# cm3.net
KiCad netlist of a schematic drawn in EAGLE
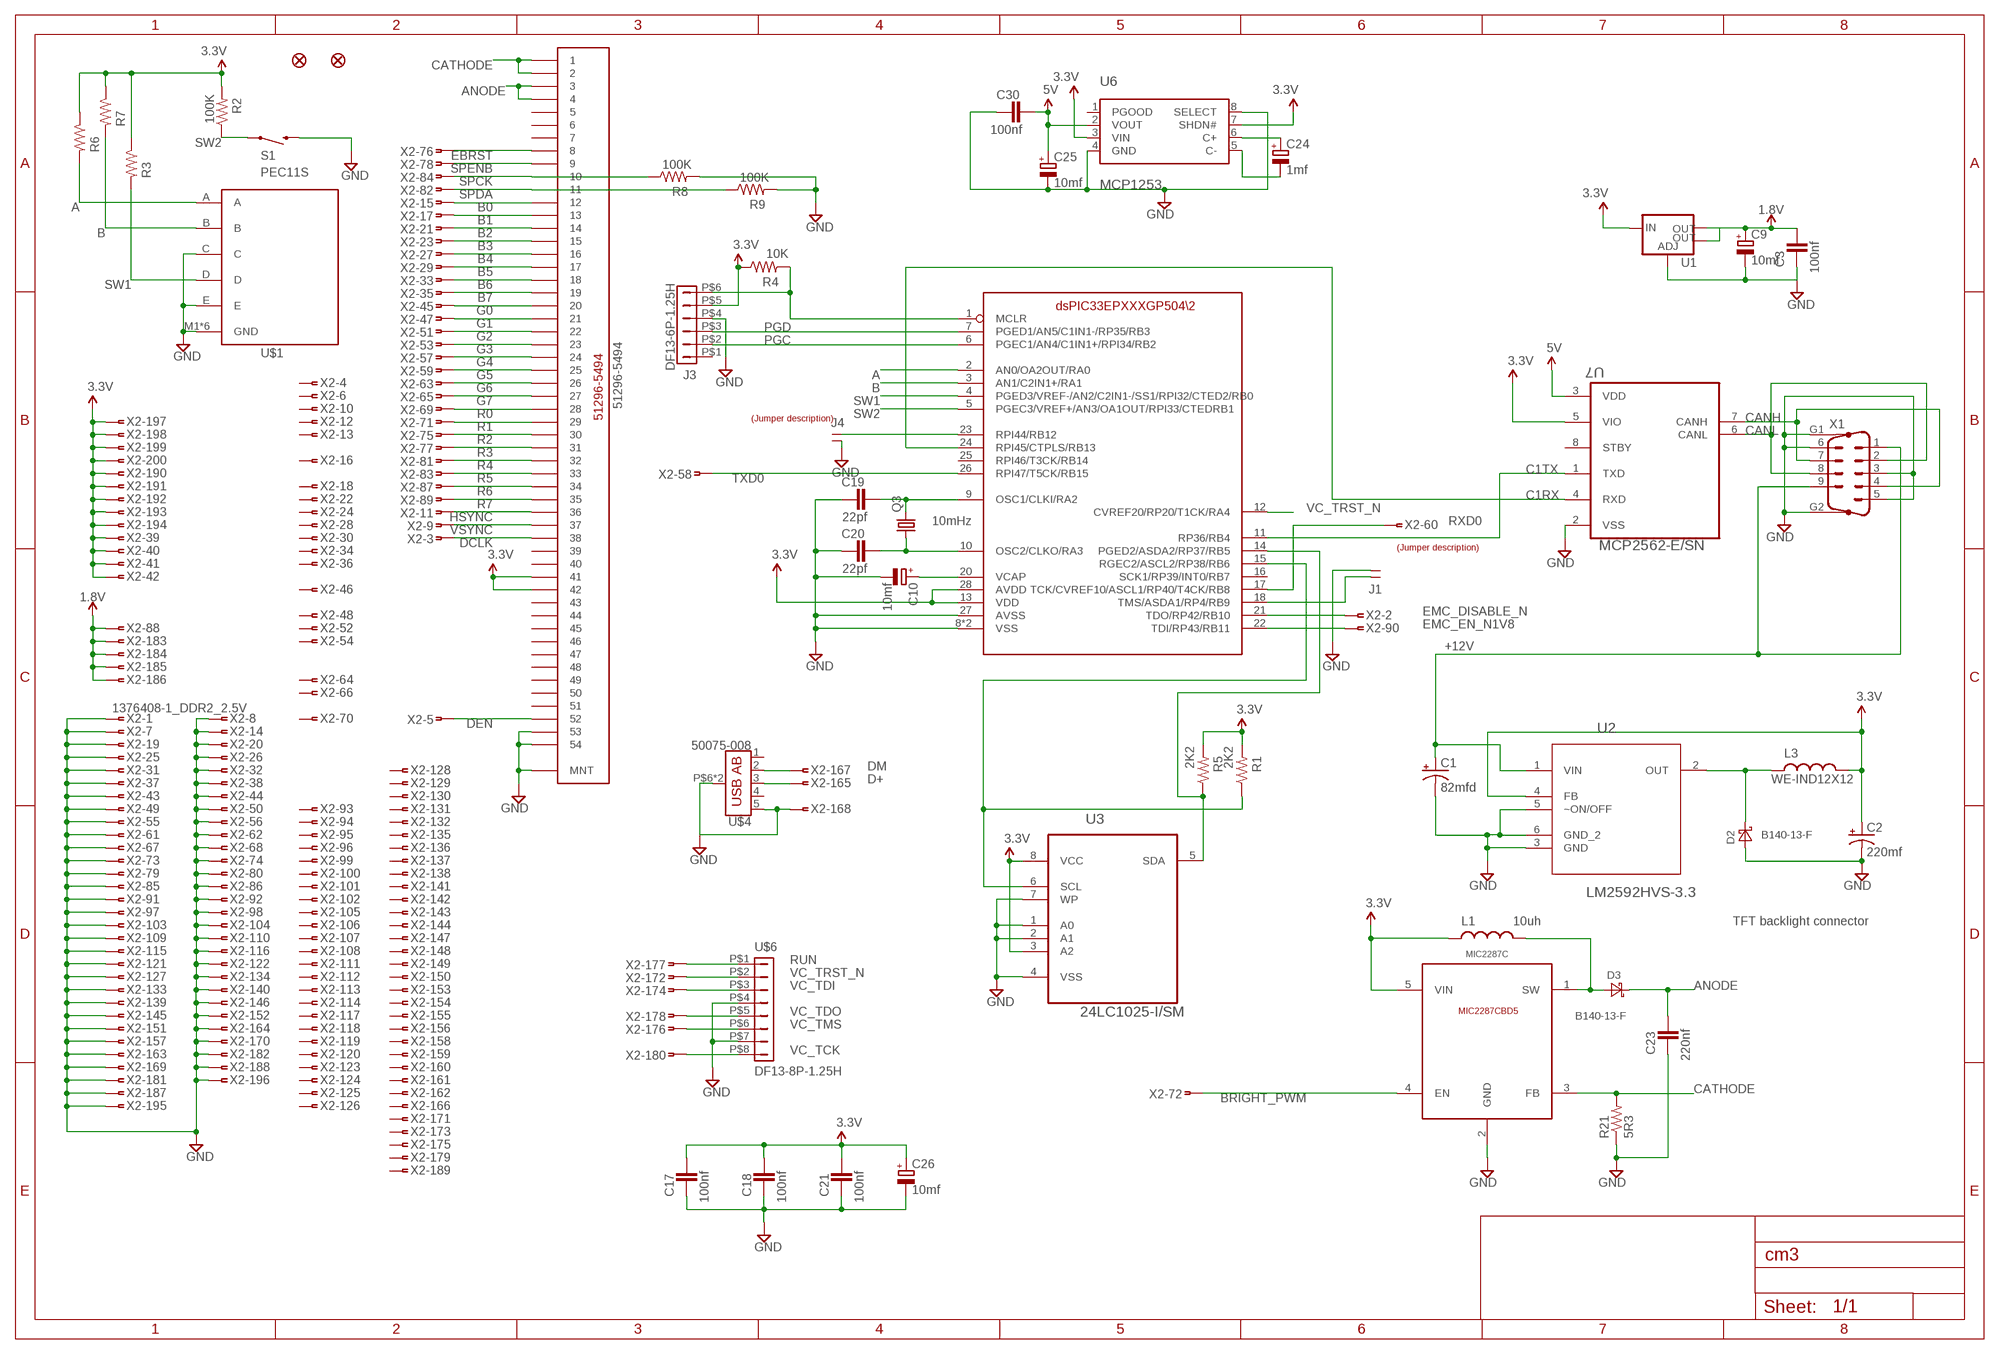
[diagram p0: schematic, sheet 1]

(export (version "E")
  (design (tool "Eeschema 10.0.6"))
  (components
    (comp (ref "C1")
      (value "82mfd")
      (footprint "eagle-import:SVPF-E7")
      (libsource (lib "eagle-import") (part "CAPACITOR_POL-SVPF-E7"))
    )
    (comp (ref "C2")
      (value "220mf")
      (footprint "eagle-import:EIA7343")
      (fields (field (name "PARTNO") "T545X227M016ATE035"))
      (libsource (lib "eagle-import") (part "CAP_POL7343"))
    )
    (comp (ref "C3")
      (value "100nf")
      (footprint "eagle-import:C805")
      (fields (field (name "PARTNO") "CL21F104ZBCNNNC"))
      (libsource (lib "eagle-import") (part "CAPACITOR_NPOL-0805"))
    )
    (comp (ref "C9")
      (value "10mf")
      (footprint "eagle-import:SMC_A")
      (fields (field (name "PARTNO") "T491A106K004AT"))
      (libsource (lib "eagle-import") (part "CAPACITOR_POL-SMC_A"))
    )
    (comp (ref "C10")
      (value "10mf")
      (footprint "eagle-import:SMC_A")
      (fields (field (name "PARTNO") "T491A106K004AT"))
      (libsource (lib "eagle-import") (part "CAPACITOR_POL-SMC_A"))
    )
    (comp (ref "C17")
      (value "100nf")
      (footprint "eagle-import:C805")
      (fields (field (name "PARTNO") "CL21F104ZBCNNNC"))
      (libsource (lib "eagle-import") (part "CAPACITOR_NPOL-0805"))
    )
    (comp (ref "C18")
      (value "100nf")
      (footprint "eagle-import:C805")
      (fields (field (name "PARTNO") "CL21F104ZBCNNNC"))
      (libsource (lib "eagle-import") (part "CAPACITOR_NPOL-0805"))
    )
    (comp (ref "C19")
      (value "22pf")
      (footprint "eagle-import:C805")
      (fields (field (name "PARTNO") "C0805C220J5GACTU"))
      (libsource (lib "eagle-import") (part "CAPACITOR_NPOL-0805"))
    )
    (comp (ref "C20")
      (value "22pf")
      (footprint "eagle-import:C805")
      (fields (field (name "PARTNO") "C0805C220J5GACTU"))
      (libsource (lib "eagle-import") (part "CAPACITOR_NPOL-0805"))
    )
    (comp (ref "C21")
      (value "100nf")
      (footprint "eagle-import:C805")
      (fields (field (name "PARTNO") "CL21F104ZBCNNNC"))
      (libsource (lib "eagle-import") (part "CAPACITOR_NPOL-0805"))
    )
    (comp (ref "C23")
      (value "220nf")
      (footprint "eagle-import:C805")
      (fields (field (name "PARTNO") "CL21F224ZBCNNNC"))
      (libsource (lib "eagle-import") (part "CAPACITOR_NPOL-0805"))
    )
    (comp (ref "C24")
      (value "1mf")
      (footprint "eagle-import:SMC_A")
      (fields (field (name "PARTNO") "F931C105MAA"))
      (libsource (lib "eagle-import") (part "CAPACITOR_POL-SMC_A"))
    )
    (comp (ref "C25")
      (value "10mf")
      (footprint "eagle-import:SMC_A")
      (fields (field (name "PARTNO") "T491A106K004AT"))
      (libsource (lib "eagle-import") (part "CAPACITOR_POL-SMC_A"))
    )
    (comp (ref "C26")
      (value "10mf")
      (footprint "eagle-import:SMC_A")
      (fields (field (name "PARTNO") "T491A106K004AT"))
      (libsource (lib "eagle-import") (part "CAPACITOR_POL-SMC_A"))
    )
    (comp (ref "C30")
      (value "100nf")
      (footprint "eagle-import:C805")
      (fields (field (name "PARTNO") "CL21F104ZBCNNNC"))
      (libsource (lib "eagle-import") (part "CAPACITOR_NPOL-0805"))
    )
    (comp (ref "D2")
      (value "B140-13-F")
      (footprint "eagle-import:SMA")
      (libsource (lib "eagle-import") (part "DIODE-SCHOTTKY-SMA"))
    )
    (comp (ref "D3")
      (value "B140-13-F")
      (footprint "eagle-import:SMA")
      (libsource (lib "eagle-import") (part "DIODE-SCHOTTKY-SMA"))
    )
    (comp (ref "J1")
      (value "JUMPER-1X2")
      (footprint "eagle-import:JUMPER-1X2")
      (fields (field (name "PARTNO") "M20-9770246"))
      (libsource (lib "eagle-import") (part "JUMPER-1X2"))
    )
    (comp (ref "J3")
      (value "DF13-6P-1.25H")
      (footprint "eagle-import:DF13A-6P-1.25H")
      (fields (field (name "PARTNO") "DF13A-6P-1.25H(20)"))
      (libsource (lib "eagle-import") (part "DF13-6P-1.25H"))
    )
    (comp (ref "J4")
      (value "JUMPER-1X2")
      (footprint "eagle-import:JUMPER-1X2")
      (fields (field (name "PARTNO") "M20-9770246"))
      (libsource (lib "eagle-import") (part "JUMPER-1X2"))
    )
    (comp (ref "JP1")
      (value "FIDUCIAL1.5X3")
      (footprint "eagle-import:FIDUCIAL-1.5X3")
      (libsource (lib "eagle-import") (part "FIDUCIAL1.5X3"))
    )
    (comp (ref "JP2")
      (value "FIDUCIAL1.5X3")
      (footprint "eagle-import:FIDUCIAL-1.5X3")
      (libsource (lib "eagle-import") (part "FIDUCIAL1.5X3"))
    )
    (comp (ref "L1")
      (value "10uh")
      (footprint "eagle-import:1812")
      (fields (field (name "PARTNO") "VLF504015MT-100M"))
      (libsource (lib "eagle-import") (part "INDUCTOR"))
    )
    (comp (ref "L3")
      (value "WE-IND12X12")
      (footprint "eagle-import:IND12X12")
      (libsource (lib "eagle-import") (part "WE-IND12X12"))
    )
    (comp (ref "Q3")
      (value "10mHz")
      (footprint "eagle-import:HC49_S")
      (fields (field (name "PARTNO") "ATS100B-E"))
      (libsource (lib "eagle-import") (part "CRYSTALHC49S"))
    )
    (comp (ref "R1")
      (value "2K2")
      (footprint "eagle-import:0603-RES")
      (fields (field (name "PARTNO") "RC0603FR-072K2L"))
      (libsource (lib "eagle-import") (part "SparkFun-Passives_RESISTOR0603-RES"))
    )
    (comp (ref "R2")
      (value "100K")
      (footprint "eagle-import:0603-RES")
      (fields (field (name "PARTNO") "RC0603JR-07100KL"))
      (libsource (lib "eagle-import") (part "SparkFun-Passives_RESISTOR0603-RES"))
    )
    (comp (ref "R3")
      (value "10K")
      (footprint "eagle-import:0603-RES")
      (fields (field (name "PARTNO") "RC0603FR-0710KL"))
      (libsource (lib "eagle-import") (part "SparkFun-Passives_RESISTOR0603-RES"))
    )
    (comp (ref "R4")
      (value "10K")
      (footprint "eagle-import:0603-RES")
      (fields (field (name "PARTNO") "RC0603FR-0710KL"))
      (libsource (lib "eagle-import") (part "SparkFun-Passives_RESISTOR0603-RES"))
    )
    (comp (ref "R5")
      (value "2K2")
      (footprint "eagle-import:0603-RES")
      (fields (field (name "PARTNO") "RC0603FR-072K2L"))
      (libsource (lib "eagle-import") (part "SparkFun-Passives_RESISTOR0603-RES"))
    )
    (comp (ref "R6")
      (value "10K")
      (footprint "eagle-import:0603-RES")
      (fields (field (name "PARTNO") "RC0603FR-0710KL"))
      (libsource (lib "eagle-import") (part "SparkFun-Passives_RESISTOR0603-RES"))
    )
    (comp (ref "R7")
      (value "10K")
      (footprint "eagle-import:0603-RES")
      (fields (field (name "PARTNO") "RC0603FR-0710KL"))
      (libsource (lib "eagle-import") (part "SparkFun-Passives_RESISTOR0603-RES"))
    )
    (comp (ref "R8")
      (value "100K")
      (footprint "eagle-import:0603-RES")
      (fields (field (name "PARTNO") "RC0603JR-07100KL"))
      (libsource (lib "eagle-import") (part "SparkFun-Passives_RESISTOR0603-RES"))
    )
    (comp (ref "R9")
      (value "100K")
      (footprint "eagle-import:0603-RES")
      (fields (field (name "PARTNO") "RC0603JR-07100KL"))
      (libsource (lib "eagle-import") (part "SparkFun-Passives_RESISTOR0603-RES"))
    )
    (comp (ref "R21")
      (value "5R3")
      (footprint "eagle-import:1812")
      (fields (field (name "PARTNO") "RL1218FK-070R604L"))
      (libsource (lib "eagle-import") (part "RESISTOR1812-RES"))
    )
    (comp (ref "S1")
      (value "SWITCH-MOMENTARY-2SMD-4")
      (footprint "eagle-import:TACTILE_SWITCH_TALL")
      (fields (field (name "PARTNO") "MJTP1138BTR"))
      (libsource (lib "eagle-import") (part "SWITCH-MOMENTARY-2SMD-4"))
    )
    (comp (ref "U$1")
      (value "PEC11S")
      (footprint "eagle-import:PEC11S")
      (fields (field (name "PARTNO") "PEC11S-9215K-H0015"))
      (libsource (lib "eagle-import") (part "PEC11S"))
    )
    (comp (ref "U$2")
      (value "51296-5494")
      (footprint "eagle-import:51296-5494")
      (libsource (lib "eagle-import") (part "51296-5494"))
    )
    (comp (ref "U$3")
      (value "LABEL_JUMPER_1X2")
      (footprint "eagle-import:JUMP2_DESC")
      (fields (field (name "OFF") "Normal") (field (name "ON") "Reset"))
      (libsource (lib "eagle-import") (part "LABEL_JUMPER_1X2"))
    )
    (comp (ref "U$4")
      (value "50075-008")
      (footprint "eagle-import:500075-008")
      (libsource (lib "eagle-import") (part "50075-008"))
    )
    (comp (ref "U$5")
      (value "LABEL_JUMPER_1X2")
      (footprint "eagle-import:JUMP2_DESC")
      (fields (field (name "OFF") "EMC Boot") (field (name "ON") "USB Boot"))
      (libsource (lib "eagle-import") (part "LABEL_JUMPER_1X2"))
    )
    (comp (ref "U$6")
      (value "DF13-8P-1.25H")
      (footprint "eagle-import:DF13A-8P-1.25H")
      (libsource (lib "eagle-import") (part "DF13-8P-1.25H"))
    )
    (comp (ref "U1")
      (value "V_REG_LM1117SOT223")
      (footprint "eagle-import:SOT223")
      (libsource (lib "eagle-import") (part "V_REG_LM1117SOT223"))
    )
    (comp (ref "U2")
      (value "LM2592HVS-3.3")
      (footprint "eagle-import:TO170P1435X457-5N")
      (fields (field (name "MPN") "LM2592HVS-5.0"))
      (libsource (lib "eagle-import") (part "LM2592HVS-5.0"))
    )
    (comp (ref "U3")
      (value "24LC1025-I/SM")
      (footprint "eagle-import:SOIC8-N_MC")
      (fields (field (name "PARTNO") "24LC1025T-I/SN"))
      (libsource (lib "eagle-import") (part "24LC1025-I/SM"))
    )
    (comp (ref "U5")
      (value "DSPIC33EPXXXGP502")
      (footprint "eagle-import:SOIC-28")
      (libsource (lib "eagle-import") (part "DSPIC33EPXXXGP502"))
    )
    (comp (ref "U6")
      (value "MCP1253")
      (footprint "eagle-import:MSOP8")
      (fields (field (name "PARTNO") "MCP1253-33X50I/MS"))
      (libsource (lib "eagle-import") (part "MCP1253"))
    )
    (comp (ref "U7")
      (value "MCP2562-E/SN")
      (footprint "eagle-import:SOIC-8N")
      (libsource (lib "eagle-import") (part "MCP2562-E/SN"))
    )
    (comp (ref "U9")
      (value "MIC2287C")
      (footprint "eagle-import:SOT-23-5")
      (fields (field (name "PARTNO") "MIC2287CYD5-TR"))
      (libsource (lib "eagle-import") (part "MIC2287C"))
    )
    (comp (ref "X1")
      (value "M09VP")
      (footprint "eagle-import:M09VP")
      (libsource (lib "eagle-import") (part "M09VP"))
    )
    (comp (ref "X2")
      (value "1376408-1_DDR2_2.5V")
      (footprint "eagle-import:6-1376408-1")
      (libsource (lib "eagle-import") (part "1376408-1_DDR2_2.5V"))
    )
  )
  (nets
    (net (code "1") (name "/+12V") (class "Default")
      (node (ref "C1") (pin "P$2") (pinfunction "+_P$2") (pintype "passive"))
      (node (ref "U2") (pin "1") (pinfunction "VIN_1") (pintype "power_in"))
      (node (ref "X1") (pin "1") (pinfunction "1_1") (pintype "passive"))
      (node (ref "X1") (pin "9") (pinfunction "9_9") (pintype "passive"))
    )
    (net (code "2") (name "/A") (class "Default")
      (node (ref "R6") (pin "2") (pinfunction "2_2") (pintype "passive"))
      (node (ref "U$1") (pin "A") (pinfunction "A_A") (pintype "bidirectional"))
      (node (ref "U5") (pin "2") (pinfunction "AN0/OA2OUT/RA0_2") (pintype "bidirectional"))
    )
    (net (code "3") (name "/ANODE") (class "Default")
      (node (ref "C23") (pin "1") (pinfunction "1_1") (pintype "passive"))
      (node (ref "D3") (pin "C") (pinfunction "C_C") (pintype "passive"))
      (node (ref "U$2") (pin "P$3") (pinfunction "3_P$3") (pintype "bidirectional"))
      (node (ref "U$2") (pin "P$4") (pinfunction "4_P$4") (pintype "bidirectional"))
    )
    (net (code "4") (name "/B") (class "Default")
      (node (ref "R7") (pin "2") (pinfunction "2_2") (pintype "passive"))
      (node (ref "U$1") (pin "B") (pinfunction "B_B") (pintype "bidirectional"))
      (node (ref "U5") (pin "3") (pinfunction "AN1/C2IN1+/RA1_3") (pintype "bidirectional"))
    )
    (net (code "5") (name "/B0") (class "Default")
      (node (ref "U$2") (pin "P$12") (pinfunction "12_P$12") (pintype "bidirectional"))
      (node (ref "X2") (pin "15") (pinfunction "1_15") (pintype "passive"))
    )
    (net (code "6") (name "/B1") (class "Default")
      (node (ref "U$2") (pin "P$13") (pinfunction "13_P$13") (pintype "bidirectional"))
      (node (ref "X2") (pin "17") (pinfunction "1_17") (pintype "passive"))
    )
    (net (code "7") (name "/B2") (class "Default")
      (node (ref "U$2") (pin "P$14") (pinfunction "14_P$14") (pintype "bidirectional"))
      (node (ref "X2") (pin "21") (pinfunction "1_21") (pintype "passive"))
    )
    (net (code "8") (name "/B3") (class "Default")
      (node (ref "U$2") (pin "P$15") (pinfunction "15_P$15") (pintype "bidirectional"))
      (node (ref "X2") (pin "23") (pinfunction "1_23") (pintype "passive"))
    )
    (net (code "9") (name "/B4") (class "Default")
      (node (ref "U$2") (pin "P$16") (pinfunction "16_P$16") (pintype "bidirectional"))
      (node (ref "X2") (pin "27") (pinfunction "1_27") (pintype "passive"))
    )
    (net (code "10") (name "/B5") (class "Default")
      (node (ref "U$2") (pin "P$17") (pinfunction "17_P$17") (pintype "bidirectional"))
      (node (ref "X2") (pin "29") (pinfunction "1_29") (pintype "passive"))
    )
    (net (code "11") (name "/B6") (class "Default")
      (node (ref "U$2") (pin "P$18") (pinfunction "18_P$18") (pintype "bidirectional"))
      (node (ref "X2") (pin "33") (pinfunction "1_33") (pintype "passive"))
    )
    (net (code "12") (name "/B7") (class "Default")
      (node (ref "U$2") (pin "P$19") (pinfunction "19_P$19") (pintype "bidirectional"))
      (node (ref "X2") (pin "35") (pinfunction "1_35") (pintype "passive"))
    )
    (net (code "13") (name "/BRIGHT_PWM") (class "Default")
      (node (ref "U9") (pin "4") (pinfunction "EN_4") (pintype "bidirectional"))
      (node (ref "X2") (pin "72") (pinfunction "1_72") (pintype "passive"))
    )
    (net (code "14") (name "/C1RX") (class "Default")
      (node (ref "U5") (pin "24") (pinfunction "RPI45/CTPLS/RB13_24") (pintype "bidirectional"))
      (node (ref "U7") (pin "4") (pinfunction "RXD_4") (pintype "output"))
    )
    (net (code "15") (name "/C1TX") (class "Default")
      (node (ref "U5") (pin "11") (pinfunction "RP36/RB4_11") (pintype "bidirectional"))
      (node (ref "U7") (pin "1") (pinfunction "TXD_1") (pintype "input"))
    )
    (net (code "16") (name "/CANH") (class "Default")
      (node (ref "U7") (pin "7") (pinfunction "CANH_7") (pintype "bidirectional"))
      (node (ref "X1") (pin "4") (pinfunction "4_4") (pintype "passive"))
      (node (ref "X1") (pin "7") (pinfunction "7_7") (pintype "passive"))
    )
    (net (code "17") (name "/CANL") (class "Default")
      (node (ref "U7") (pin "6") (pinfunction "CANL_6") (pintype "bidirectional"))
      (node (ref "X1") (pin "2") (pinfunction "2_2") (pintype "passive"))
      (node (ref "X1") (pin "8") (pinfunction "8_8") (pintype "passive"))
    )
    (net (code "18") (name "/CATHODE") (class "Default")
      (node (ref "R21") (pin "2") (pinfunction "2_2") (pintype "passive"))
      (node (ref "U$2") (pin "P$1") (pinfunction "1_P$1") (pintype "bidirectional"))
      (node (ref "U$2") (pin "P$2") (pinfunction "2_P$2") (pintype "bidirectional"))
      (node (ref "U9") (pin "3") (pinfunction "FB_3") (pintype "bidirectional"))
    )
    (net (code "19") (name "/D+") (class "Default")
      (node (ref "U$4") (pin "3") (pinfunction "D+_3") (pintype "bidirectional"))
      (node (ref "X2") (pin "165") (pinfunction "1_165") (pintype "passive"))
    )
    (net (code "20") (name "/DCLK") (class "Default")
      (node (ref "U$2") (pin "P$38") (pinfunction "38_P$38") (pintype "bidirectional"))
      (node (ref "X2") (pin "3") (pinfunction "1_3") (pintype "passive"))
    )
    (net (code "21") (name "/DEN") (class "Default")
      (node (ref "U$2") (pin "P$52") (pinfunction "52_P$52") (pintype "bidirectional"))
      (node (ref "X2") (pin "5") (pinfunction "1_5") (pintype "passive"))
    )
    (net (code "22") (name "/DM") (class "Default")
      (node (ref "U$4") (pin "2") (pinfunction "D-_2") (pintype "bidirectional"))
      (node (ref "X2") (pin "167") (pinfunction "1_167") (pintype "passive"))
    )
    (net (code "23") (name "/EBRST") (class "Default")
      (node (ref "U$2") (pin "P$8") (pinfunction "8_P$8") (pintype "bidirectional"))
      (node (ref "X2") (pin "76") (pinfunction "1_76") (pintype "passive"))
    )
    (net (code "24") (name "/EMC_DISABLE_N") (class "Default")
      (node (ref "U5") (pin "21") (pinfunction "TDO/RP42/RB10_21") (pintype "bidirectional"))
      (node (ref "X2") (pin "2") (pinfunction "1_2") (pintype "passive"))
    )
    (net (code "25") (name "/EMC_EN_N1V8") (class "Default")
      (node (ref "U5") (pin "22") (pinfunction "TDI/RP43/RB11_22") (pintype "bidirectional"))
      (node (ref "X2") (pin "90") (pinfunction "1_90") (pintype "passive"))
    )
    (net (code "26") (name "/G0") (class "Default")
      (node (ref "U$2") (pin "P$20") (pinfunction "20_P$20") (pintype "bidirectional"))
      (node (ref "X2") (pin "45") (pinfunction "1_45") (pintype "passive"))
    )
    (net (code "27") (name "/G1") (class "Default")
      (node (ref "U$2") (pin "P$21") (pinfunction "21_P$21") (pintype "bidirectional"))
      (node (ref "X2") (pin "47") (pinfunction "1_47") (pintype "passive"))
    )
    (net (code "28") (name "/G2") (class "Default")
      (node (ref "U$2") (pin "P$22") (pinfunction "22_P$22") (pintype "bidirectional"))
      (node (ref "X2") (pin "51") (pinfunction "1_51") (pintype "passive"))
    )
    (net (code "29") (name "/G3") (class "Default")
      (node (ref "U$2") (pin "P$23") (pinfunction "23_P$23") (pintype "bidirectional"))
      (node (ref "X2") (pin "53") (pinfunction "1_53") (pintype "passive"))
    )
    (net (code "30") (name "/G4") (class "Default")
      (node (ref "U$2") (pin "P$24") (pinfunction "24_P$24") (pintype "bidirectional"))
      (node (ref "X2") (pin "57") (pinfunction "1_57") (pintype "passive"))
    )
    (net (code "31") (name "/G5") (class "Default")
      (node (ref "U$2") (pin "P$25") (pinfunction "25_P$25") (pintype "bidirectional"))
      (node (ref "X2") (pin "59") (pinfunction "1_59") (pintype "passive"))
    )
    (net (code "32") (name "/G6") (class "Default")
      (node (ref "U$2") (pin "P$26") (pinfunction "26_P$26") (pintype "bidirectional"))
      (node (ref "X2") (pin "63") (pinfunction "1_63") (pintype "passive"))
    )
    (net (code "33") (name "/G7") (class "Default")
      (node (ref "U$2") (pin "P$27") (pinfunction "27_P$27") (pintype "bidirectional"))
      (node (ref "X2") (pin "65") (pinfunction "1_65") (pintype "passive"))
    )
    (net (code "34") (name "/HSYNC") (class "Default")
      (node (ref "U$2") (pin "P$36") (pinfunction "36_P$36") (pintype "bidirectional"))
      (node (ref "X2") (pin "11") (pinfunction "1_11") (pintype "passive"))
    )
    (net (code "35") (name "/PGC") (class "Default")
      (node (ref "J3") (pin "P$2") (pinfunction "2_P$2") (pintype "passive"))
      (node (ref "U5") (pin "6") (pinfunction "PGEC1/AN4/C1IN1+/RPI34/RB2_6") (pintype "bidirectional"))
    )
    (net (code "36") (name "/PGD") (class "Default")
      (node (ref "J3") (pin "P$3") (pinfunction "3_P$3") (pintype "passive"))
      (node (ref "U5") (pin "7") (pinfunction "PGED1/AN5/C1IN1-/RP35/RB3_7") (pintype "bidirectional"))
    )
    (net (code "37") (name "/R0") (class "Default")
      (node (ref "U$2") (pin "P$28") (pinfunction "28_P$28") (pintype "bidirectional"))
      (node (ref "X2") (pin "69") (pinfunction "1_69") (pintype "passive"))
    )
    (net (code "38") (name "/R1") (class "Default")
      (node (ref "U$2") (pin "P$29") (pinfunction "29_P$29") (pintype "bidirectional"))
      (node (ref "X2") (pin "71") (pinfunction "1_71") (pintype "passive"))
    )
    (net (code "39") (name "/R2") (class "Default")
      (node (ref "U$2") (pin "P$30") (pinfunction "30_P$30") (pintype "bidirectional"))
      (node (ref "X2") (pin "75") (pinfunction "1_75") (pintype "passive"))
    )
    (net (code "40") (name "/R3") (class "Default")
      (node (ref "U$2") (pin "P$31") (pinfunction "31_P$31") (pintype "bidirectional"))
      (node (ref "X2") (pin "77") (pinfunction "1_77") (pintype "passive"))
    )
    (net (code "41") (name "/R4") (class "Default")
      (node (ref "U$2") (pin "P$32") (pinfunction "32_P$32") (pintype "bidirectional"))
      (node (ref "X2") (pin "81") (pinfunction "1_81") (pintype "passive"))
    )
    (net (code "42") (name "/R5") (class "Default")
      (node (ref "U$2") (pin "P$33") (pinfunction "33_P$33") (pintype "bidirectional"))
      (node (ref "X2") (pin "83") (pinfunction "1_83") (pintype "passive"))
    )
    (net (code "43") (name "/R6") (class "Default")
      (node (ref "U$2") (pin "P$34") (pinfunction "34_P$34") (pintype "bidirectional"))
      (node (ref "X2") (pin "87") (pinfunction "1_87") (pintype "passive"))
    )
    (net (code "44") (name "/R7") (class "Default")
      (node (ref "U$2") (pin "P$35") (pinfunction "35_P$35") (pintype "bidirectional"))
      (node (ref "X2") (pin "89") (pinfunction "1_89") (pintype "passive"))
    )
    (net (code "45") (name "/RUN") (class "Default")
      (node (ref "U$6") (pin "P$1") (pinfunction "1_P$1") (pintype "passive"))
      (node (ref "X2") (pin "177") (pinfunction "1_177") (pintype "passive"))
    )
    (net (code "46") (name "/RXD0") (class "Default")
      (node (ref "U5") (pin "17") (pinfunction "TCK/CVREF10/ASCL1/RP40/T4CK/RB8_17") (pintype "bidirectional"))
      (node (ref "X2") (pin "60") (pinfunction "1_60") (pintype "passive"))
    )
    (net (code "47") (name "/SPCK") (class "Default")
      (node (ref "R8") (pin "1") (pinfunction "1_1") (pintype "passive"))
      (node (ref "U$2") (pin "P$10") (pinfunction "10_P$10") (pintype "bidirectional"))
      (node (ref "X2") (pin "84") (pinfunction "1_84") (pintype "passive"))
    )
    (net (code "48") (name "/SPDA") (class "Default")
      (node (ref "R9") (pin "1") (pinfunction "1_1") (pintype "passive"))
      (node (ref "U$2") (pin "P$11") (pinfunction "11_P$11") (pintype "bidirectional"))
      (node (ref "X2") (pin "82") (pinfunction "1_82") (pintype "passive"))
    )
    (net (code "49") (name "/SPENB") (class "Default")
      (node (ref "U$2") (pin "P$9") (pinfunction "9_P$9") (pintype "bidirectional"))
      (node (ref "X2") (pin "78") (pinfunction "1_78") (pintype "passive"))
    )
    (net (code "50") (name "/SW1") (class "Default")
      (node (ref "R3") (pin "2") (pinfunction "2_2") (pintype "passive"))
      (node (ref "U$1") (pin "D") (pinfunction "D_D") (pintype "bidirectional"))
      (node (ref "U5") (pin "4") (pinfunction "PGED3/VREF-/AN2/C2IN1-/SS1/RPI32/CTED2/RB0_4") (pintype "bidirectional"))
    )
    (net (code "51") (name "/SW2") (class "Default")
      (node (ref "R2") (pin "1") (pinfunction "1_1") (pintype "passive"))
      (node (ref "S1") (pin "A2") (pinfunction "1_A2") (pintype "passive"))
      (node (ref "U5") (pin "5") (pinfunction "PGEC3/VREF+/AN3/OA1OUT/RPI33/CTEDRB1_5") (pintype "bidirectional"))
    )
    (net (code "52") (name "/TXD0") (class "Default")
      (node (ref "U5") (pin "26") (pinfunction "RPI47/T5CK/RB15_26") (pintype "bidirectional"))
      (node (ref "X2") (pin "58") (pinfunction "1_58") (pintype "passive"))
    )
    (net (code "53") (name "/VBUS") (class "Default")
      (node (ref "U$4") (pin "1") (pinfunction "VBUS_1") (pintype "power_in"))
    )
    (net (code "54") (name "/VC_TCK") (class "Default")
      (node (ref "U$6") (pin "P$8") (pinfunction "8_P$8") (pintype "passive"))
      (node (ref "X2") (pin "180") (pinfunction "1_180") (pintype "passive"))
    )
    (net (code "55") (name "/VC_TDI") (class "Default")
      (node (ref "U$6") (pin "P$3") (pinfunction "3_P$3") (pintype "passive"))
      (node (ref "X2") (pin "174") (pinfunction "1_174") (pintype "passive"))
    )
    (net (code "56") (name "/VC_TDO") (class "Default")
      (node (ref "U$6") (pin "P$5") (pinfunction "5_P$5") (pintype "passive"))
      (node (ref "X2") (pin "178") (pinfunction "1_178") (pintype "passive"))
    )
    (net (code "57") (name "/VC_TMS") (class "Default")
      (node (ref "U$6") (pin "P$6") (pinfunction "6_P$6") (pintype "passive"))
      (node (ref "X2") (pin "176") (pinfunction "1_176") (pintype "passive"))
    )
    (net (code "58") (name "/VC_TRST_N") (class "Default")
      (node (ref "U$6") (pin "P$2") (pinfunction "2_P$2") (pintype "passive"))
      (node (ref "U5") (pin "12") (pinfunction "CVREF20/RP20/T1CK/RA4_12") (pintype "bidirectional"))
      (node (ref "X2") (pin "172") (pinfunction "1_172") (pintype "passive"))
    )
    (net (code "59") (name "/VSYNC") (class "Default")
      (node (ref "U$2") (pin "P$37") (pinfunction "37_P$37") (pintype "bidirectional"))
      (node (ref "X2") (pin "9") (pinfunction "1_9") (pintype "passive"))
    )
    (net (code "60") (name "1.8V") (class "Default")
      (node (ref "C3") (pin "1") (pinfunction "1_1") (pintype "passive"))
      (node (ref "C9") (pin "+") (pinfunction "+_+") (pintype "passive"))
      (node (ref "U1") (pin "2") (pinfunction "OUT_2") (pintype "output"))
      (node (ref "U1") (pin "4") (pinfunction "OUT_4") (pintype "output"))
      (node (ref "X2") (pin "183") (pinfunction "1_183") (pintype "passive"))
      (node (ref "X2") (pin "184") (pinfunction "1_184") (pintype "passive"))
      (node (ref "X2") (pin "185") (pinfunction "1_185") (pintype "passive"))
      (node (ref "X2") (pin "186") (pinfunction "1_186") (pintype "passive"))
      (node (ref "X2") (pin "88") (pinfunction "1_88") (pintype "passive"))
    )
    (net (code "61") (name "3.3V") (class "Default")
      (node (ref "C17") (pin "1") (pinfunction "1_1") (pintype "passive"))
      (node (ref "C18") (pin "1") (pinfunction "1_1") (pintype "passive"))
      (node (ref "C2") (pin "A") (pinfunction "+_A") (pintype "passive"))
      (node (ref "C21") (pin "1") (pinfunction "1_1") (pintype "passive"))
      (node (ref "C26") (pin "+") (pinfunction "+_+") (pintype "passive"))
      (node (ref "J3") (pin "P$5") (pinfunction "5_P$5") (pintype "passive"))
      (node (ref "L1") (pin "1") (pinfunction "1_1") (pintype "passive"))
      (node (ref "L3") (pin "P$2") (pinfunction "2_P$2") (pintype "passive"))
      (node (ref "R1") (pin "2") (pinfunction "2_2") (pintype "passive"))
      (node (ref "R2") (pin "2") (pinfunction "2_2") (pintype "passive"))
      (node (ref "R3") (pin "1") (pinfunction "1_1") (pintype "passive"))
      (node (ref "R4") (pin "1") (pinfunction "1_1") (pintype "passive"))
      (node (ref "R5") (pin "2") (pinfunction "2_2") (pintype "passive"))
      (node (ref "R6") (pin "1") (pinfunction "1_1") (pintype "passive"))
      (node (ref "R7") (pin "1") (pinfunction "1_1") (pintype "passive"))
      (node (ref "U$2") (pin "P$41") (pinfunction "41_P$41") (pintype "bidirectional"))
      (node (ref "U$2") (pin "P$42") (pinfunction "42_P$42") (pintype "bidirectional"))
      (node (ref "U1") (pin "3") (pinfunction "IN_3") (pintype "input"))
      (node (ref "U2") (pin "4") (pinfunction "FB_4") (pintype "input"))
      (node (ref "U3") (pin "3") (pinfunction "A2_3") (pintype "input"))
      (node (ref "U3") (pin "8") (pinfunction "VCC_8") (pintype "power_in"))
      (node (ref "U5") (pin "13") (pinfunction "VDD_13") (pintype "bidirectional"))
      (node (ref "U5") (pin "28") (pinfunction "AVDD_28") (pintype "bidirectional"))
      (node (ref "U6") (pin "3") (pinfunction "VIN_3") (pintype "power_in"))
      (node (ref "U6") (pin "7") (pinfunction "SHDN#_7") (pintype "input"))
      (node (ref "U7") (pin "5") (pinfunction "VIO_5") (pintype "power_in"))
      (node (ref "U9") (pin "5") (pinfunction "VIN_5") (pintype "bidirectional"))
      (node (ref "X2") (pin "190") (pinfunction "1_190") (pintype "passive"))
      (node (ref "X2") (pin "191") (pinfunction "1_191") (pintype "passive"))
      (node (ref "X2") (pin "192") (pinfunction "1_192") (pintype "passive"))
      (node (ref "X2") (pin "193") (pinfunction "1_193") (pintype "passive"))
      (node (ref "X2") (pin "194") (pinfunction "1_194") (pintype "passive"))
      (node (ref "X2") (pin "197") (pinfunction "1_197") (pintype "passive"))
      (node (ref "X2") (pin "198") (pinfunction "1_198") (pintype "passive"))
      (node (ref "X2") (pin "199") (pinfunction "1_199") (pintype "passive"))
      (node (ref "X2") (pin "200") (pinfunction "1_200") (pintype "passive"))
      (node (ref "X2") (pin "39") (pinfunction "1_39") (pintype "passive"))
      (node (ref "X2") (pin "40") (pinfunction "1_40") (pintype "passive"))
      (node (ref "X2") (pin "41") (pinfunction "1_41") (pintype "passive"))
      (node (ref "X2") (pin "42") (pinfunction "1_42") (pintype "passive"))
    )
    (net (code "62") (name "5V") (class "Default")
      (node (ref "C25") (pin "+") (pinfunction "+_+") (pintype "passive"))
      (node (ref "C30") (pin "1") (pinfunction "1_1") (pintype "passive"))
      (node (ref "U6") (pin "2") (pinfunction "VOUT_2") (pintype "power_in"))
      (node (ref "U7") (pin "3") (pinfunction "VDD_3") (pintype "power_in"))
    )
    (net (code "63") (name "GND") (class "Default")
      (node (ref "C1") (pin "P$1") (pinfunction "-_P$1") (pintype "passive"))
      (node (ref "C10") (pin "-") (pinfunction "-_-") (pintype "passive"))
      (node (ref "C17") (pin "2") (pinfunction "2_2") (pintype "passive"))
      (node (ref "C18") (pin "2") (pinfunction "2_2") (pintype "passive"))
      (node (ref "C19") (pin "2") (pinfunction "2_2") (pintype "passive"))
      (node (ref "C2") (pin "C") (pinfunction "-_C") (pintype "passive"))
      (node (ref "C20") (pin "2") (pinfunction "2_2") (pintype "passive"))
      (node (ref "C21") (pin "2") (pinfunction "2_2") (pintype "passive"))
      (node (ref "C23") (pin "2") (pinfunction "2_2") (pintype "passive"))
      (node (ref "C25") (pin "-") (pinfunction "-_-") (pintype "passive"))
      (node (ref "C26") (pin "-") (pinfunction "-_-") (pintype "passive"))
      (node (ref "C3") (pin "2") (pinfunction "2_2") (pintype "passive"))
      (node (ref "C30") (pin "2") (pinfunction "2_2") (pintype "passive"))
      (node (ref "C9") (pin "-") (pinfunction "-_-") (pintype "passive"))
      (node (ref "D2") (pin "A") (pinfunction "A_A") (pintype "passive"))
      (node (ref "J1") (pin "2") (pinfunction "2_2") (pintype "bidirectional"))
      (node (ref "J3") (pin "P$4") (pinfunction "4_P$4") (pintype "passive"))
      (node (ref "J4") (pin "2") (pinfunction "2_2") (pintype "bidirectional"))
      (node (ref "R21") (pin "1") (pinfunction "1_1") (pintype "passive"))
      (node (ref "R8") (pin "2") (pinfunction "2_2") (pintype "passive"))
      (node (ref "R9") (pin "2") (pinfunction "2_2") (pintype "passive"))
      (node (ref "S1") (pin "B2") (pinfunction "2_B2") (pintype "passive"))
      (node (ref "U$1") (pin "C") (pinfunction "C_C") (pintype "bidirectional"))
      (node (ref "U$1") (pin "E") (pinfunction "E_E") (pintype "bidirectional"))
      (node (ref "U$1") (pin "M1") (pinfunction "GND_M1") (pintype "bidirectional"))
      (node (ref "U$1") (pin "M2") (pinfunction "GND_M2") (pintype "bidirectional"))
      (node (ref "U$1") (pin "M3") (pinfunction "GND_M3") (pintype "bidirectional"))
      (node (ref "U$1") (pin "M4") (pinfunction "GND_M4") (pintype "bidirectional"))
      (node (ref "U$1") (pin "M5") (pinfunction "GND_M5") (pintype "bidirectional"))
      (node (ref "U$1") (pin "M6") (pinfunction "GND_M6") (pintype "bidirectional"))
      (node (ref "U$2") (pin "MNT1") (pinfunction "MNT_MNT1") (pintype "bidirectional"))
      (node (ref "U$2") (pin "MNT2") (pinfunction "MNT_MNT2") (pintype "bidirectional"))
      (node (ref "U$2") (pin "P$53") (pinfunction "53_P$53") (pintype "bidirectional"))
      (node (ref "U$2") (pin "P$54") (pinfunction "54_P$54") (pintype "bidirectional"))
      (node (ref "U$4") (pin "5") (pinfunction "GND_5") (pintype "power_in"))
      (node (ref "U$4") (pin "P$6") (pinfunction "SHIELD_P$6") (pintype "bidirectional"))
      (node (ref "U$4") (pin "P$7") (pinfunction "SHIELD_P$7") (pintype "bidirectional"))
      (node (ref "U$6") (pin "P$4") (pinfunction "4_P$4") (pintype "passive"))
      (node (ref "U$6") (pin "P$7") (pinfunction "7_P$7") (pintype "passive"))
      (node (ref "U1") (pin "1") (pinfunction "ADJ_1") (pintype "input"))
      (node (ref "U2") (pin "3") (pinfunction "GND_3") (pintype "passive"))
      (node (ref "U2") (pin "5") (pinfunction "~{ON/OFF}_5") (pintype "input"))
      (node (ref "U2") (pin "6") (pinfunction "GND_2_6") (pintype "passive"))
      (node (ref "U3") (pin "1") (pinfunction "A0_1") (pintype "input"))
      (node (ref "U3") (pin "2") (pinfunction "A1_2") (pintype "input"))
      (node (ref "U3") (pin "4") (pinfunction "VSS_4") (pintype "passive"))
      (node (ref "U3") (pin "7") (pinfunction "WP_7") (pintype "input"))
      (node (ref "U5") (pin "19") (pinfunction "VSS_19") (pintype "bidirectional"))
      (node (ref "U5") (pin "27") (pinfunction "AVSS_27") (pintype "bidirectional"))
      (node (ref "U5") (pin "8") (pinfunction "VSS_8") (pintype "bidirectional"))
      (node (ref "U6") (pin "4") (pinfunction "GND_4") (pintype "power_in"))
      (node (ref "U6") (pin "8") (pinfunction "SELECT_8") (pintype "input"))
      (node (ref "U7") (pin "2") (pinfunction "VSS_2") (pintype "power_in"))
      (node (ref "U9") (pin "2") (pinfunction "GND_2") (pintype "bidirectional"))
      (node (ref "X1") (pin "3") (pinfunction "3_3") (pintype "passive"))
      (node (ref "X1") (pin "5") (pinfunction "5_5") (pintype "passive"))
      (node (ref "X1") (pin "6") (pinfunction "6_6") (pintype "passive"))
      (node (ref "X1") (pin "G1") (pinfunction "G1_G1") (pintype "passive"))
      (node (ref "X1") (pin "G2") (pinfunction "G2_G2") (pintype "passive"))
      (node (ref "X2") (pin "1") (pinfunction "1_1") (pintype "passive"))
      (node (ref "X2") (pin "103") (pinfunction "1_103") (pintype "passive"))
      (node (ref "X2") (pin "104") (pinfunction "1_104") (pintype "passive"))
      (node (ref "X2") (pin "109") (pinfunction "1_109") (pintype "passive"))
      (node (ref "X2") (pin "110") (pinfunction "1_110") (pintype "passive"))
      (node (ref "X2") (pin "115") (pinfunction "1_115") (pintype "passive"))
      (node (ref "X2") (pin "116") (pinfunction "1_116") (pintype "passive"))
      (node (ref "X2") (pin "121") (pinfunction "1_121") (pintype "passive"))
      (node (ref "X2") (pin "122") (pinfunction "1_122") (pintype "passive"))
      (node (ref "X2") (pin "127") (pinfunction "1_127") (pintype "passive"))
      (node (ref "X2") (pin "133") (pinfunction "1_133") (pintype "passive"))
      (node (ref "X2") (pin "134") (pinfunction "1_134") (pintype "passive"))
      (node (ref "X2") (pin "139") (pinfunction "1_139") (pintype "passive"))
      (node (ref "X2") (pin "14") (pinfunction "1_14") (pintype "passive"))
      (node (ref "X2") (pin "140") (pinfunction "1_140") (pintype "passive"))
      (node (ref "X2") (pin "145") (pinfunction "1_145") (pintype "passive"))
      (node (ref "X2") (pin "146") (pinfunction "1_146") (pintype "passive"))
      (node (ref "X2") (pin "151") (pinfunction "1_151") (pintype "passive"))
      (node (ref "X2") (pin "152") (pinfunction "1_152") (pintype "passive"))
      (node (ref "X2") (pin "157") (pinfunction "1_157") (pintype "passive"))
      (node (ref "X2") (pin "163") (pinfunction "1_163") (pintype "passive"))
      (node (ref "X2") (pin "164") (pinfunction "1_164") (pintype "passive"))
      (node (ref "X2") (pin "168") (pinfunction "1_168") (pintype "passive"))
      (node (ref "X2") (pin "169") (pinfunction "1_169") (pintype "passive"))
      (node (ref "X2") (pin "170") (pinfunction "1_170") (pintype "passive"))
      (node (ref "X2") (pin "181") (pinfunction "1_181") (pintype "passive"))
      (node (ref "X2") (pin "182") (pinfunction "1_182") (pintype "passive"))
      (node (ref "X2") (pin "187") (pinfunction "1_187") (pintype "passive"))
      (node (ref "X2") (pin "188") (pinfunction "1_188") (pintype "passive"))
      (node (ref "X2") (pin "19") (pinfunction "1_19") (pintype "passive"))
      (node (ref "X2") (pin "195") (pinfunction "1_195") (pintype "passive"))
      (node (ref "X2") (pin "196") (pinfunction "1_196") (pintype "passive"))
      (node (ref "X2") (pin "20") (pinfunction "1_20") (pintype "passive"))
      (node (ref "X2") (pin "25") (pinfunction "1_25") (pintype "passive"))
      (node (ref "X2") (pin "26") (pinfunction "1_26") (pintype "passive"))
      (node (ref "X2") (pin "31") (pinfunction "1_31") (pintype "passive"))
      (node (ref "X2") (pin "32") (pinfunction "1_32") (pintype "passive"))
      (node (ref "X2") (pin "37") (pinfunction "1_37") (pintype "passive"))
      (node (ref "X2") (pin "38") (pinfunction "1_38") (pintype "passive"))
      (node (ref "X2") (pin "43") (pinfunction "1_43") (pintype "passive"))
      (node (ref "X2") (pin "44") (pinfunction "1_44") (pintype "passive"))
      (node (ref "X2") (pin "49") (pinfunction "1_49") (pintype "passive"))
      (node (ref "X2") (pin "50") (pinfunction "1_50") (pintype "passive"))
      (node (ref "X2") (pin "55") (pinfunction "1_55") (pintype "passive"))
      (node (ref "X2") (pin "56") (pinfunction "1_56") (pintype "passive"))
      (node (ref "X2") (pin "61") (pinfunction "1_61") (pintype "passive"))
      (node (ref "X2") (pin "62") (pinfunction "1_62") (pintype "passive"))
      (node (ref "X2") (pin "67") (pinfunction "1_67") (pintype "passive"))
      (node (ref "X2") (pin "68") (pinfunction "1_68") (pintype "passive"))
      (node (ref "X2") (pin "7") (pinfunction "1_7") (pintype "passive"))
      (node (ref "X2") (pin "73") (pinfunction "1_73") (pintype "passive"))
      (node (ref "X2") (pin "74") (pinfunction "1_74") (pintype "passive"))
      (node (ref "X2") (pin "79") (pinfunction "1_79") (pintype "passive"))
      (node (ref "X2") (pin "8") (pinfunction "1_8") (pintype "passive"))
      (node (ref "X2") (pin "80") (pinfunction "1_80") (pintype "passive"))
      (node (ref "X2") (pin "85") (pinfunction "1_85") (pintype "passive"))
      (node (ref "X2") (pin "86") (pinfunction "1_86") (pintype "passive"))
      (node (ref "X2") (pin "91") (pinfunction "1_91") (pintype "passive"))
      (node (ref "X2") (pin "92") (pinfunction "1_92") (pintype "passive"))
      (node (ref "X2") (pin "97") (pinfunction "1_97") (pintype "passive"))
      (node (ref "X2") (pin "98") (pinfunction "1_98") (pintype "passive"))
    )
    (net (code "64") (name "Net-(J3-6)") (class "Default")
      (node (ref "J3") (pin "P$6") (pinfunction "6_P$6") (pintype "passive"))
      (node (ref "R4") (pin "2") (pinfunction "2_2") (pintype "passive"))
      (node (ref "U5") (pin "1") (pinfunction "MCLR_1") (pintype "input"))
    )
    (net (code "65") (name "Net-(L3-1)") (class "Default")
      (node (ref "D2") (pin "C") (pinfunction "C_C") (pintype "passive"))
      (node (ref "L3") (pin "P$1") (pinfunction "1_P$1") (pintype "passive"))
      (node (ref "U2") (pin "2") (pinfunction "OUT_2") (pintype "output"))
    )
    (net (code "66") (name "Net-(U3-SCL)") (class "Default")
      (node (ref "R1") (pin "1") (pinfunction "1_1") (pintype "passive"))
      (node (ref "U3") (pin "6") (pinfunction "SCL_6") (pintype "input"))
      (node (ref "U5") (pin "15") (pinfunction "RGEC2/ASCL2/RP38/RB6_15") (pintype "bidirectional"))
    )
    (net (code "67") (name "Net-(U3-SDA)") (class "Default")
      (node (ref "R5") (pin "1") (pinfunction "1_1") (pintype "passive"))
      (node (ref "U3") (pin "5") (pinfunction "SDA_5") (pintype "bidirectional"))
      (node (ref "U5") (pin "14") (pinfunction "PGED2/ASDA2/RP37/RB5_14") (pintype "bidirectional"))
    )
    (net (code "68") (name "Net-(U5-OSC1{slash}CLKI{slash}RA2)") (class "Default")
      (node (ref "C19") (pin "1") (pinfunction "1_1") (pintype "passive"))
      (node (ref "Q3") (pin "2") (pinfunction "2_2") (pintype "passive"))
      (node (ref "U5") (pin "9") (pinfunction "OSC1/CLKI/RA2_9") (pintype "bidirectional"))
    )
    (net (code "69") (name "Net-(U5-OSC2{slash}CLKO{slash}RA3)") (class "Default")
      (node (ref "C20") (pin "1") (pinfunction "1_1") (pintype "passive"))
      (node (ref "Q3") (pin "1") (pinfunction "1_1") (pintype "passive"))
      (node (ref "U5") (pin "10") (pinfunction "OSC2/CLKO/RA3_10") (pintype "bidirectional"))
    )
    (net (code "70") (name "Net-(U5-RPI44{slash}RB12)") (class "Default")
      (node (ref "J4") (pin "1") (pinfunction "1_1") (pintype "bidirectional"))
      (node (ref "U5") (pin "23") (pinfunction "RPI44/RB12_23") (pintype "bidirectional"))
    )
    (net (code "71") (name "Net-(U5-TMS{slash}ASDA1{slash}RP4{slash}RB9)") (class "Default")
      (node (ref "J1") (pin "1") (pinfunction "1_1") (pintype "bidirectional"))
      (node (ref "U5") (pin "18") (pinfunction "TMS/ASDA1/RP4/RB9_18") (pintype "bidirectional"))
    )
    (net (code "72") (name "Net-(U5-VCAP)") (class "Default")
      (node (ref "C10") (pin "+") (pinfunction "+_+") (pintype "passive"))
      (node (ref "U5") (pin "20") (pinfunction "VCAP_20") (pintype "bidirectional"))
    )
    (net (code "73") (name "Net-(U6-C+)") (class "Default")
      (node (ref "C24") (pin "+") (pinfunction "+_+") (pintype "passive"))
      (node (ref "U6") (pin "6") (pinfunction "C+_6") (pintype "passive"))
    )
    (net (code "74") (name "Net-(U6-C-)") (class "Default")
      (node (ref "C24") (pin "-") (pinfunction "-_-") (pintype "passive"))
      (node (ref "U6") (pin "5") (pinfunction "C-_5") (pintype "passive"))
    )
    (net (code "75") (name "Net-(U9-SW)") (class "Default")
      (node (ref "D3") (pin "A") (pinfunction "A_A") (pintype "passive"))
      (node (ref "L1") (pin "2") (pinfunction "2_2") (pintype "passive"))
      (node (ref "U9") (pin "1") (pinfunction "SW_1") (pintype "bidirectional"))
    )
    (net (code "76") (name "unconnected-(J3-1-PadP$1)") (class "Default")
      (node (ref "J3") (pin "P$1") (pinfunction "1_P$1") (pintype "passive"))
    )
    (net (code "77") (name "unconnected-(U$2-5-PadP$5)") (class "Default")
      (node (ref "U$2") (pin "P$5") (pinfunction "5_P$5") (pintype "bidirectional"))
    )
    (net (code "78") (name "unconnected-(U$2-6-PadP$6)") (class "Default")
      (node (ref "U$2") (pin "P$6") (pinfunction "6_P$6") (pintype "bidirectional"))
    )
    (net (code "79") (name "unconnected-(U$2-7-PadP$7)") (class "Default")
      (node (ref "U$2") (pin "P$7") (pinfunction "7_P$7") (pintype "bidirectional"))
    )
    (net (code "80") (name "unconnected-(U$2-39-PadP$39)") (class "Default")
      (node (ref "U$2") (pin "P$39") (pinfunction "39_P$39") (pintype "bidirectional"))
    )
    (net (code "81") (name "unconnected-(U$2-40-PadP$40)") (class "Default")
      (node (ref "U$2") (pin "P$40") (pinfunction "40_P$40") (pintype "bidirectional"))
    )
    (net (code "82") (name "unconnected-(U$2-43-PadP$43)") (class "Default")
      (node (ref "U$2") (pin "P$43") (pinfunction "43_P$43") (pintype "bidirectional"))
    )
    (net (code "83") (name "unconnected-(U$2-44-PadP$44)") (class "Default")
      (node (ref "U$2") (pin "P$44") (pinfunction "44_P$44") (pintype "bidirectional"))
    )
    (net (code "84") (name "unconnected-(U$2-45-PadP$45)") (class "Default")
      (node (ref "U$2") (pin "P$45") (pinfunction "45_P$45") (pintype "bidirectional"))
    )
    (net (code "85") (name "unconnected-(U$2-46-PadP$46)") (class "Default")
      (node (ref "U$2") (pin "P$46") (pinfunction "46_P$46") (pintype "bidirectional"))
    )
    (net (code "86") (name "unconnected-(U$2-47-PadP$47)") (class "Default")
      (node (ref "U$2") (pin "P$47") (pinfunction "47_P$47") (pintype "bidirectional"))
    )
    (net (code "87") (name "unconnected-(U$2-48-PadP$48)") (class "Default")
      (node (ref "U$2") (pin "P$48") (pinfunction "48_P$48") (pintype "bidirectional"))
    )
    (net (code "88") (name "unconnected-(U$2-49-PadP$49)") (class "Default")
      (node (ref "U$2") (pin "P$49") (pinfunction "49_P$49") (pintype "bidirectional"))
    )
    (net (code "89") (name "unconnected-(U$2-50-PadP$50)") (class "Default")
      (node (ref "U$2") (pin "P$50") (pinfunction "50_P$50") (pintype "bidirectional"))
    )
    (net (code "90") (name "unconnected-(U$2-51-PadP$51)") (class "Default")
      (node (ref "U$2") (pin "P$51") (pinfunction "51_P$51") (pintype "bidirectional"))
    )
    (net (code "91") (name "unconnected-(U$4-USBID-Pad4)") (class "Default")
      (node (ref "U$4") (pin "4") (pinfunction "USBID_4") (pintype "bidirectional"))
    )
    (net (code "92") (name "unconnected-(U5-RPI46{slash}T3CK{slash}RB14-Pad25)") (class "Default")
      (node (ref "U5") (pin "25") (pinfunction "RPI46/T3CK/RB14_25") (pintype "bidirectional"))
    )
    (net (code "93") (name "unconnected-(U5-SCK1{slash}RP39{slash}INT0{slash}RB7-Pad16)") (class "Default")
      (node (ref "U5") (pin "16") (pinfunction "SCK1/RP39/INT0/RB7_16") (pintype "bidirectional"))
    )
    (net (code "94") (name "unconnected-(U6-PGOOD-Pad1)") (class "Default")
      (node (ref "U6") (pin "1") (pinfunction "PGOOD_1") (pintype "open_collector"))
    )
    (net (code "95") (name "unconnected-(U7-STBY-Pad8)") (class "Default")
      (node (ref "U7") (pin "8") (pinfunction "STBY_8") (pintype "input"))
    )
    (net (code "96") (name "unconnected-(X2AB-1-Pad123)") (class "Default")
      (node (ref "X2") (pin "123") (pinfunction "1_123") (pintype "passive"))
    )
    (net (code "97") (name "unconnected-(X2AC-1-Pad124)") (class "Default")
      (node (ref "X2") (pin "124") (pinfunction "1_124") (pintype "passive"))
    )
    (net (code "98") (name "unconnected-(X2AD-1-Pad125)") (class "Default")
      (node (ref "X2") (pin "125") (pinfunction "1_125") (pintype "passive"))
    )
    (net (code "99") (name "unconnected-(X2AE-1-Pad126)") (class "Default")
      (node (ref "X2") (pin "126") (pinfunction "1_126") (pintype "passive"))
    )
    (net (code "100") (name "unconnected-(X2AG-1-Pad128)") (class "Default")
      (node (ref "X2") (pin "128") (pinfunction "1_128") (pintype "passive"))
    )
    (net (code "101") (name "unconnected-(X2AH-1-Pad129)") (class "Default")
      (node (ref "X2") (pin "129") (pinfunction "1_129") (pintype "passive"))
    )
    (net (code "102") (name "unconnected-(X2AI-1-Pad13)") (class "Default")
      (node (ref "X2") (pin "13") (pinfunction "1_13") (pintype "passive"))
    )
    (net (code "103") (name "unconnected-(X2AJ-1-Pad130)") (class "Default")
      (node (ref "X2") (pin "130") (pinfunction "1_130") (pintype "passive"))
    )
    (net (code "104") (name "unconnected-(X2AK-1-Pad131)") (class "Default")
      (node (ref "X2") (pin "131") (pinfunction "1_131") (pintype "passive"))
    )
    (net (code "105") (name "unconnected-(X2AL-1-Pad132)") (class "Default")
      (node (ref "X2") (pin "132") (pinfunction "1_132") (pintype "passive"))
    )
    (net (code "106") (name "unconnected-(X2AO-1-Pad135)") (class "Default")
      (node (ref "X2") (pin "135") (pinfunction "1_135") (pintype "passive"))
    )
    (net (code "107") (name "unconnected-(X2AP-1-Pad136)") (class "Default")
      (node (ref "X2") (pin "136") (pinfunction "1_136") (pintype "passive"))
    )
    (net (code "108") (name "unconnected-(X2AQ-1-Pad137)") (class "Default")
      (node (ref "X2") (pin "137") (pinfunction "1_137") (pintype "passive"))
    )
    (net (code "109") (name "unconnected-(X2AR-1-Pad138)") (class "Default")
      (node (ref "X2") (pin "138") (pinfunction "1_138") (pintype "passive"))
    )
    (net (code "110") (name "unconnected-(X2AV-1-Pad141)") (class "Default")
      (node (ref "X2") (pin "141") (pinfunction "1_141") (pintype "passive"))
    )
    (net (code "111") (name "unconnected-(X2AW-1-Pad142)") (class "Default")
      (node (ref "X2") (pin "142") (pinfunction "1_142") (pintype "passive"))
    )
    (net (code "112") (name "unconnected-(X2AX-1-Pad143)") (class "Default")
      (node (ref "X2") (pin "143") (pinfunction "1_143") (pintype "passive"))
    )
    (net (code "113") (name "unconnected-(X2AY-1-Pad144)") (class "Default")
      (node (ref "X2") (pin "144") (pinfunction "1_144") (pintype "passive"))
    )
    (net (code "114") (name "unconnected-(X2B-1-Pad10)") (class "Default")
      (node (ref "X2") (pin "10") (pinfunction "1_10") (pintype "passive"))
    )
    (net (code "115") (name "unconnected-(X2BB-1-Pad147)") (class "Default")
      (node (ref "X2") (pin "147") (pinfunction "1_147") (pintype "passive"))
    )
    (net (code "116") (name "unconnected-(X2BC-1-Pad148)") (class "Default")
      (node (ref "X2") (pin "148") (pinfunction "1_148") (pintype "passive"))
    )
    (net (code "117") (name "unconnected-(X2BD-1-Pad149)") (class "Default")
      (node (ref "X2") (pin "149") (pinfunction "1_149") (pintype "passive"))
    )
    (net (code "118") (name "unconnected-(X2BF-1-Pad150)") (class "Default")
      (node (ref "X2") (pin "150") (pinfunction "1_150") (pintype "passive"))
    )
    (net (code "119") (name "unconnected-(X2BI-1-Pad153)") (class "Default")
      (node (ref "X2") (pin "153") (pinfunction "1_153") (pintype "passive"))
    )
    (net (code "120") (name "unconnected-(X2BJ-1-Pad154)") (class "Default")
      (node (ref "X2") (pin "154") (pinfunction "1_154") (pintype "passive"))
    )
    (net (code "121") (name "unconnected-(X2BK-1-Pad155)") (class "Default")
      (node (ref "X2") (pin "155") (pinfunction "1_155") (pintype "passive"))
    )
    (net (code "122") (name "unconnected-(X2BL-1-Pad156)") (class "Default")
      (node (ref "X2") (pin "156") (pinfunction "1_156") (pintype "passive"))
    )
    (net (code "123") (name "unconnected-(X2BN-1-Pad158)") (class "Default")
      (node (ref "X2") (pin "158") (pinfunction "1_158") (pintype "passive"))
    )
    (net (code "124") (name "unconnected-(X2BO-1-Pad159)") (class "Default")
      (node (ref "X2") (pin "159") (pinfunction "1_159") (pintype "passive"))
    )
    (net (code "125") (name "unconnected-(X2BP-1-Pad16)") (class "Default")
      (node (ref "X2") (pin "16") (pinfunction "1_16") (pintype "passive"))
    )
    (net (code "126") (name "unconnected-(X2BQ-1-Pad160)") (class "Default")
      (node (ref "X2") (pin "160") (pinfunction "1_160") (pintype "passive"))
    )
    (net (code "127") (name "unconnected-(X2BR-1-Pad161)") (class "Default")
      (node (ref "X2") (pin "161") (pinfunction "1_161") (pintype "passive"))
    )
    (net (code "128") (name "unconnected-(X2BS-1-Pad162)") (class "Default")
      (node (ref "X2") (pin "162") (pinfunction "1_162") (pintype "passive"))
    )
    (net (code "129") (name "unconnected-(X2BW-1-Pad166)") (class "Default")
      (node (ref "X2") (pin "166") (pinfunction "1_166") (pintype "passive"))
    )
    (net (code "130") (name "unconnected-(X2C-1-Pad100)") (class "Default")
      (node (ref "X2") (pin "100") (pinfunction "1_100") (pintype "passive"))
    )
    (net (code "131") (name "unconnected-(X2CC-1-Pad171)") (class "Default")
      (node (ref "X2") (pin "171") (pinfunction "1_171") (pintype "passive"))
    )
    (net (code "132") (name "unconnected-(X2CE-1-Pad173)") (class "Default")
      (node (ref "X2") (pin "173") (pinfunction "1_173") (pintype "passive"))
    )
    (net (code "133") (name "unconnected-(X2CG-1-Pad175)") (class "Default")
      (node (ref "X2") (pin "175") (pinfunction "1_175") (pintype "passive"))
    )
    (net (code "134") (name "unconnected-(X2CK-1-Pad179)") (class "Default")
      (node (ref "X2") (pin "179") (pinfunction "1_179") (pintype "passive"))
    )
    (net (code "135") (name "unconnected-(X2CL-1-Pad18)") (class "Default")
      (node (ref "X2") (pin "18") (pinfunction "1_18") (pintype "passive"))
    )
    (net (code "136") (name "unconnected-(X2CV-1-Pad189)") (class "Default")
      (node (ref "X2") (pin "189") (pinfunction "1_189") (pintype "passive"))
    )
    (net (code "137") (name "unconnected-(X2D-1-Pad101)") (class "Default")
      (node (ref "X2") (pin "101") (pinfunction "1_101") (pintype "passive"))
    )
    (net (code "138") (name "unconnected-(X2DL-1-Pad22)") (class "Default")
      (node (ref "X2") (pin "22") (pinfunction "1_22") (pintype "passive"))
    )
    (net (code "139") (name "unconnected-(X2DN-1-Pad24)") (class "Default")
      (node (ref "X2") (pin "24") (pinfunction "1_24") (pintype "passive"))
    )
    (net (code "140") (name "unconnected-(X2DR-1-Pad28)") (class "Default")
      (node (ref "X2") (pin "28") (pinfunction "1_28") (pintype "passive"))
    )
    (net (code "141") (name "unconnected-(X2DU-1-Pad30)") (class "Default")
      (node (ref "X2") (pin "30") (pinfunction "1_30") (pintype "passive"))
    )
    (net (code "142") (name "unconnected-(X2DY-1-Pad34)") (class "Default")
      (node (ref "X2") (pin "34") (pinfunction "1_34") (pintype "passive"))
    )
    (net (code "143") (name "unconnected-(X2E-1-Pad102)") (class "Default")
      (node (ref "X2") (pin "102") (pinfunction "1_102") (pintype "passive"))
    )
    (net (code "144") (name "unconnected-(X2EA-1-Pad36)") (class "Default")
      (node (ref "X2") (pin "36") (pinfunction "1_36") (pintype "passive"))
    )
    (net (code "145") (name "unconnected-(X2EE-1-Pad4)") (class "Default")
      (node (ref "X2") (pin "4") (pinfunction "1_4") (pintype "passive"))
    )
    (net (code "146") (name "unconnected-(X2EL-1-Pad46)") (class "Default")
      (node (ref "X2") (pin "46") (pinfunction "1_46") (pintype "passive"))
    )
    (net (code "147") (name "unconnected-(X2EN-1-Pad48)") (class "Default")
      (node (ref "X2") (pin "48") (pinfunction "1_48") (pintype "passive"))
    )
    (net (code "148") (name "unconnected-(X2ES-1-Pad52)") (class "Default")
      (node (ref "X2") (pin "52") (pinfunction "1_52") (pintype "passive"))
    )
    (net (code "149") (name "unconnected-(X2EU-1-Pad54)") (class "Default")
      (node (ref "X2") (pin "54") (pinfunction "1_54") (pintype "passive"))
    )
    (net (code "150") (name "unconnected-(X2FA-1-Pad6)") (class "Default")
      (node (ref "X2") (pin "6") (pinfunction "1_6") (pintype "passive"))
    )
    (net (code "151") (name "unconnected-(X2FF-1-Pad64)") (class "Default")
      (node (ref "X2") (pin "64") (pinfunction "1_64") (pintype "passive"))
    )
    (net (code "152") (name "unconnected-(X2FH-1-Pad66)") (class "Default")
      (node (ref "X2") (pin "66") (pinfunction "1_66") (pintype "passive"))
    )
    (net (code "153") (name "unconnected-(X2FM-1-Pad70)") (class "Default")
      (node (ref "X2") (pin "70") (pinfunction "1_70") (pintype "passive"))
    )
    (net (code "154") (name "unconnected-(X2GL-1-Pad93)") (class "Default")
      (node (ref "X2") (pin "93") (pinfunction "1_93") (pintype "passive"))
    )
    (net (code "155") (name "unconnected-(X2GM-1-Pad94)") (class "Default")
      (node (ref "X2") (pin "94") (pinfunction "1_94") (pintype "passive"))
    )
    (net (code "156") (name "unconnected-(X2GN-1-Pad95)") (class "Default")
      (node (ref "X2") (pin "95") (pinfunction "1_95") (pintype "passive"))
    )
    (net (code "157") (name "unconnected-(X2GO-1-Pad96)") (class "Default")
      (node (ref "X2") (pin "96") (pinfunction "1_96") (pintype "passive"))
    )
    (net (code "158") (name "unconnected-(X2GR-1-Pad99)") (class "Default")
      (node (ref "X2") (pin "99") (pinfunction "1_99") (pintype "passive"))
    )
    (net (code "159") (name "unconnected-(X2H-1-Pad105)") (class "Default")
      (node (ref "X2") (pin "105") (pinfunction "1_105") (pintype "passive"))
    )
    (net (code "160") (name "unconnected-(X2I-1-Pad106)") (class "Default")
      (node (ref "X2") (pin "106") (pinfunction "1_106") (pintype "passive"))
    )
    (net (code "161") (name "unconnected-(X2J-1-Pad107)") (class "Default")
      (node (ref "X2") (pin "107") (pinfunction "1_107") (pintype "passive"))
    )
    (net (code "162") (name "unconnected-(X2K-1-Pad108)") (class "Default")
      (node (ref "X2") (pin "108") (pinfunction "1_108") (pintype "passive"))
    )
    (net (code "163") (name "unconnected-(X2O-1-Pad111)") (class "Default")
      (node (ref "X2") (pin "111") (pinfunction "1_111") (pintype "passive"))
    )
    (net (code "164") (name "unconnected-(X2P-1-Pad112)") (class "Default")
      (node (ref "X2") (pin "112") (pinfunction "1_112") (pintype "passive"))
    )
    (net (code "165") (name "unconnected-(X2Q-1-Pad113)") (class "Default")
      (node (ref "X2") (pin "113") (pinfunction "1_113") (pintype "passive"))
    )
    (net (code "166") (name "unconnected-(X2R-1-Pad114)") (class "Default")
      (node (ref "X2") (pin "114") (pinfunction "1_114") (pintype "passive"))
    )
    (net (code "167") (name "unconnected-(X2U-1-Pad117)") (class "Default")
      (node (ref "X2") (pin "117") (pinfunction "1_117") (pintype "passive"))
    )
    (net (code "168") (name "unconnected-(X2V-1-Pad118)") (class "Default")
      (node (ref "X2") (pin "118") (pinfunction "1_118") (pintype "passive"))
    )
    (net (code "169") (name "unconnected-(X2W-1-Pad119)") (class "Default")
      (node (ref "X2") (pin "119") (pinfunction "1_119") (pintype "passive"))
    )
    (net (code "170") (name "unconnected-(X2X-1-Pad12)") (class "Default")
      (node (ref "X2") (pin "12") (pinfunction "1_12") (pintype "passive"))
    )
    (net (code "171") (name "unconnected-(X2Y-1-Pad120)") (class "Default")
      (node (ref "X2") (pin "120") (pinfunction "1_120") (pintype "passive"))
    )
  )
)
